# SH4_-_3_3V_LINEAR_REGULATOR.net
KiCad netlist of a schematic drawn in Altium Designer
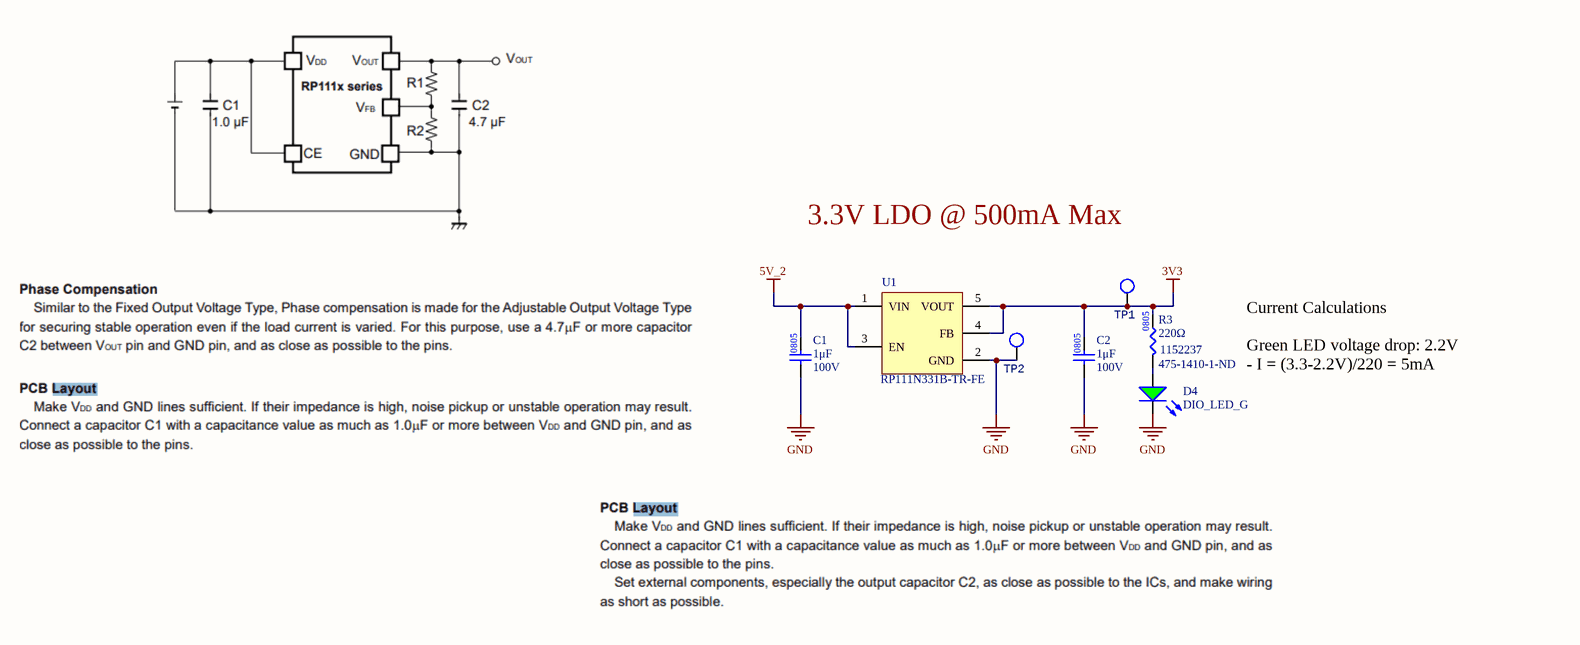
[diagram p0: SH4 - 3.3V LINEAR REGULATOR.SchDoc]

(export (version "E")
  (design (tool "Eeschema 10.0.6"))
  (components
    (comp (ref "C1")
      (value "1μF")
      (footprint "CAP0805")
      (description "CAP CER 1UF 100V X7S 0805")
      (fields (field (name "VOLTAGE RATING") "100V") (field (name "Comment") "CAP_1uF_100V_0805"))
      (libsource (lib "UWRT_Schematic_Library_2020") (part "CAP_1uF_100V_0805"))
    )
    (comp (ref "C2")
      (value "1μF")
      (footprint "CAP0805")
      (description "CAP CER 1UF 100V X7S 0805")
      (fields (field (name "VOLTAGE RATING") "100V") (field (name "Comment") "CAP_1uF_100V_0805"))
      (libsource (lib "UWRT_Schematic_Library_2020") (part "CAP_1uF_100V_0805"))
    )
    (comp (ref "D4")
      (value "DIO_LED_G")
      (footprint "LED_0805_GREEN")
      (description "LED GREEN DIFFUSED 0805 SMD")
      (fields
        (field (name "SUPPLIER PART NUMBER 1") "475-1410-1-ND")
        (field (name "SUPPLIER PART NUMBER 2") "1152237")
      )
      (libsource (lib "UWRT_Schematic_Library_2020") (part "DIO_LED_G"))
    )
    (comp (ref "R3")
      (value "220Ω")
      (footprint "RES0805")
      (description "RES 220 OHM 5% 1/2W 0805")
      (fields (field (name "LCSC PART #") "C17557") (field (name "Comment") "RES_220Ω_0805_5%"))
      (libsource (lib "UWRT_Schematic_Library_2020") (part "RES_220Ω_0805_5%"))
    )
    (comp (ref "TP1")
      (value "TESTPOINT_LOOP")
      (footprint "TESTPOINT_LOOP")
      (description "TESTPOINT THRUHOLE")
      (libsource (lib "UWRT_Schematic_Library_2020") (part "TESTPOINT_LOOP"))
    )
    (comp (ref "TP2")
      (value "TESTPOINT_LOOP")
      (footprint "TESTPOINT_LOOP")
      (description "TESTPOINT THRUHOLE")
      (libsource (lib "UWRT_Schematic_Library_2020") (part "TESTPOINT_LOOP"))
    )
    (comp (ref "U1")
      (value "LDO_3.3V_500mA")
      (footprint "SOT23-5")
      (description "IC REG LINEAR 3.3V 500MA SOT23-5")
      (fields (field (name "MANUFACTURER PART NUMBER 1") "RP111N331B-TR-FE"))
      (libsource (lib "UWRT_Schematic_Library_2020") (part "LDO_3.3V_500mA"))
    )
  )
  (nets
    (net (code "1") (name "3V3") (class "Default")
      (node (ref "C2") (pin "2") (pinfunction "2_2") (pintype "passive"))
      (node (ref "R3") (pin "2") (pinfunction "2_2") (pintype "passive"))
      (node (ref "TP1") (pin "1") (pintype "passive"))
      (node (ref "U1") (pin "4") (pinfunction "FB_4") (pintype "passive"))
      (node (ref "U1") (pin "5") (pinfunction "VOUT_5") (pintype "passive"))
    )
    (net (code "2") (name "5V_2") (class "Default")
      (node (ref "C1") (pin "2") (pinfunction "2_2") (pintype "passive"))
      (node (ref "U1") (pin "1") (pinfunction "VIN_1") (pintype "passive"))
      (node (ref "U1") (pin "3") (pinfunction "EN_3") (pintype "passive"))
    )
    (net (code "3") (name "GND") (class "Default")
      (node (ref "C1") (pin "1") (pinfunction "1_1") (pintype "passive"))
      (node (ref "C2") (pin "1") (pinfunction "1_1") (pintype "passive"))
      (node (ref "D4") (pin "2") (pinfunction "K_2") (pintype "passive"))
      (node (ref "TP2") (pin "1") (pintype "passive"))
      (node (ref "U1") (pin "2") (pinfunction "GND_2") (pintype "passive"))
    )
    (net (code "4") (name "Net-(D4-A)") (class "Default")
      (node (ref "D4") (pin "1") (pinfunction "A_1") (pintype "passive"))
      (node (ref "R3") (pin "1") (pinfunction "1_1") (pintype "passive"))
    )
  )
)
